# eBox_ACdetect2.net
KiCad netlist of a schematic drawn in Altium Designer
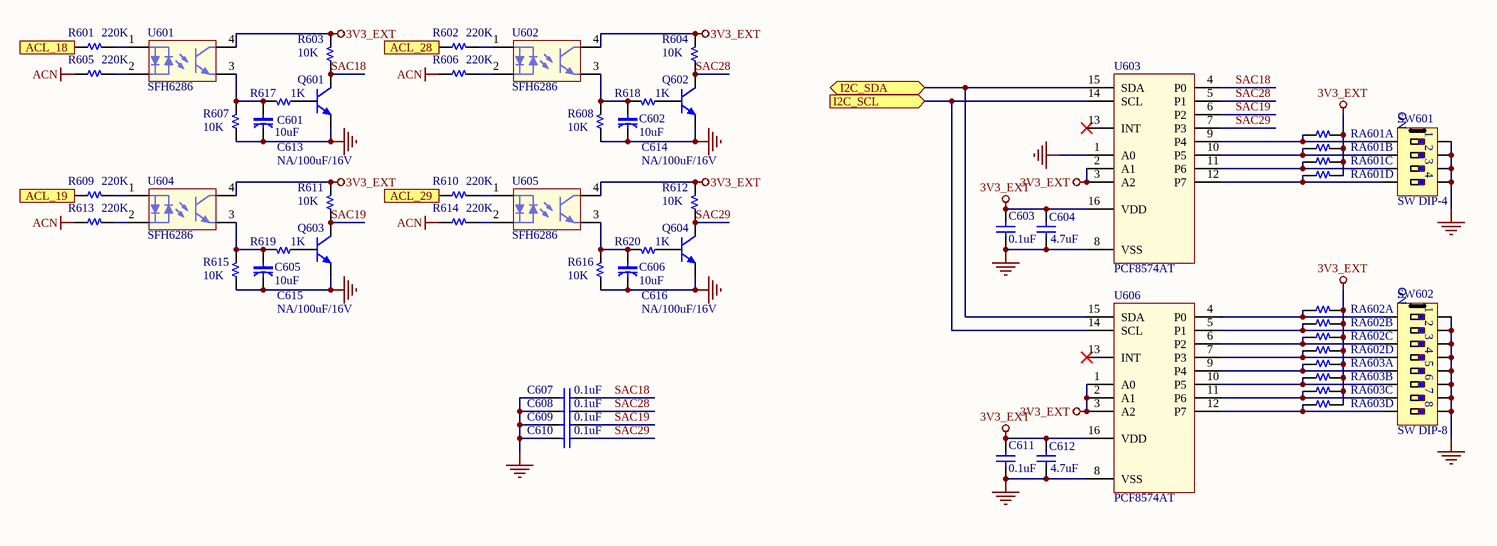
[diagram p0: eBox_ACdetect2.SchDoc]

(export (version "E")
  (design (tool "Eeschema 10.0.6"))
  (components
    (comp (ref "C601")
      (value "10uF")
      (footprint "C 0805")
      (description "CAP CER 0.1UF 50V X7R 0805")
      (libsource (lib "chipfc_altium_libs") (part "Capacitor NP"))
    )
    (comp (ref "C602")
      (value "10uF")
      (footprint "C 0805")
      (description "CAP CER 0.1UF 50V X7R 0805")
      (libsource (lib "chipfc_altium_libs") (part "Capacitor NP"))
    )
    (comp (ref "C603")
      (value "0.1uF")
      (footprint "C 0603")
      (description "CAP CER 0.1UF 50V X7R 0603")
      (libsource (lib "chipfc_altium_libs") (part "Capacitor NP"))
    )
    (comp (ref "C604")
      (value "4.7uF")
      (footprint "C 0603")
      (description "CAP CER 4.7UF 50V X7R 0603")
      (libsource (lib "chipfc_altium_libs") (part "Capacitor NP"))
    )
    (comp (ref "C605")
      (value "10uF")
      (footprint "C 0805")
      (description "CAP CER 0.1UF 50V X7R 0805")
      (libsource (lib "chipfc_altium_libs") (part "Capacitor NP"))
    )
    (comp (ref "C606")
      (value "10uF")
      (footprint "C 0805")
      (description "CAP CER 0.1UF 50V X7R 0805")
      (libsource (lib "chipfc_altium_libs") (part "Capacitor NP"))
    )
    (comp (ref "C607")
      (value "0.1uF")
      (footprint "C 0805")
      (description "CAP CER 0.1UF 50V X7R 0805")
      (libsource (lib "chipfc_altium_libs") (part "Capacitor NP"))
    )
    (comp (ref "C608")
      (value "0.1uF")
      (footprint "C 0805")
      (description "CAP CER 0.1UF 50V X7R 0805")
      (libsource (lib "chipfc_altium_libs") (part "Capacitor NP"))
    )
    (comp (ref "C609")
      (value "0.1uF")
      (footprint "C 0805")
      (description "CAP CER 0.1UF 50V X7R 0805")
      (libsource (lib "chipfc_altium_libs") (part "Capacitor NP"))
    )
    (comp (ref "C610")
      (value "0.1uF")
      (footprint "C 0805")
      (description "CAP CER 0.1UF 50V X7R 0805")
      (libsource (lib "chipfc_altium_libs") (part "Capacitor NP"))
    )
    (comp (ref "C611")
      (value "0.1uF")
      (footprint "C 0603")
      (description "CAP CER 0.1UF 50V X7R 0603")
      (libsource (lib "chipfc_altium_libs") (part "Capacitor NP"))
    )
    (comp (ref "C612")
      (value "4.7uF")
      (footprint "C 0603")
      (description "CAP CER 4.7UF 50V X7R 0603")
      (libsource (lib "chipfc_altium_libs") (part "Capacitor NP"))
    )
    (comp (ref "C613")
      (value "NA/100uF/16V")
      (footprint "CYL/D.200/LS.75-D50H70P20")
      (description "CAP ALUM 100UF 20% 16V RADIAL")
      (libsource (lib "chipfc_altium_libs") (part "Capacitor"))
    )
    (comp (ref "C614")
      (value "NA/100uF/16V")
      (footprint "CYL/D.200/LS.75-D50H70P20")
      (description "CAP ALUM 100UF 20% 16V RADIAL")
      (libsource (lib "chipfc_altium_libs") (part "Capacitor"))
    )
    (comp (ref "C615")
      (value "NA/100uF/16V")
      (footprint "CYL/D.200/LS.75-D50H70P20")
      (description "CAP ALUM 100UF 20% 16V RADIAL")
      (libsource (lib "chipfc_altium_libs") (part "Capacitor"))
    )
    (comp (ref "C616")
      (value "NA/100uF/16V")
      (footprint "CYL/D.200/LS.75-D50H70P20")
      (description "CAP ALUM 100UF 20% 16V RADIAL")
      (libsource (lib "chipfc_altium_libs") (part "Capacitor"))
    )
    (comp (ref "Q601")
      (value "MMBT3904LT1G")
      (footprint "SOT-23")
      (description "TRANS NPN 40V 0.2A SOT23")
      (libsource (lib "chipfc_altium_libs") (part "Transistor NPN"))
    )
    (comp (ref "Q602")
      (value "MMBT3904LT1G")
      (footprint "SOT-23")
      (description "TRANS NPN 40V 0.2A SOT23")
      (libsource (lib "chipfc_altium_libs") (part "Transistor NPN"))
    )
    (comp (ref "Q603")
      (value "MMBT3904LT1G")
      (footprint "SOT-23")
      (description "TRANS NPN 40V 0.2A SOT23")
      (libsource (lib "chipfc_altium_libs") (part "Transistor NPN"))
    )
    (comp (ref "Q604")
      (value "MMBT3904LT1G")
      (footprint "SOT-23")
      (description "TRANS NPN 40V 0.2A SOT23")
      (libsource (lib "chipfc_altium_libs") (part "Transistor NPN"))
    )
    (comp (ref "R601")
      (value "220K")
      (footprint "R 0805")
      (description "RES SMD 220K OHM 1% 1/8W 0805")
      (libsource (lib "chipfc_altium_libs") (part "Resistor"))
    )
    (comp (ref "R602")
      (value "220K")
      (footprint "R 0805")
      (description "RES SMD 220K OHM 1% 1/8W 0805")
      (libsource (lib "chipfc_altium_libs") (part "Resistor"))
    )
    (comp (ref "R603")
      (value "10K")
      (footprint "R 0805")
      (description "RES SMD 10K OHM 1% 1/8W 0805")
      (libsource (lib "chipfc_altium_libs") (part "Resistor"))
    )
    (comp (ref "R604")
      (value "10K")
      (footprint "R 0805")
      (description "RES SMD 10K OHM 1% 1/8W 0805")
      (libsource (lib "chipfc_altium_libs") (part "Resistor"))
    )
    (comp (ref "R605")
      (value "220K")
      (footprint "R 0805")
      (description "RES SMD 220K OHM 1% 1/8W 0805")
      (libsource (lib "chipfc_altium_libs") (part "Resistor"))
    )
    (comp (ref "R606")
      (value "220K")
      (footprint "R 0805")
      (description "RES SMD 220K OHM 1% 1/8W 0805")
      (libsource (lib "chipfc_altium_libs") (part "Resistor"))
    )
    (comp (ref "R607")
      (value "10K")
      (footprint "R 0805")
      (description "RES SMD 10K OHM 1% 1/8W 0805")
      (libsource (lib "chipfc_altium_libs") (part "Resistor"))
    )
    (comp (ref "R608")
      (value "10K")
      (footprint "R 0805")
      (description "RES SMD 10K OHM 1% 1/8W 0805")
      (libsource (lib "chipfc_altium_libs") (part "Resistor"))
    )
    (comp (ref "R609")
      (value "220K")
      (footprint "R 0805")
      (description "RES SMD 220K OHM 1% 1/8W 0805")
      (libsource (lib "chipfc_altium_libs") (part "Resistor"))
    )
    (comp (ref "R610")
      (value "220K")
      (footprint "R 0805")
      (description "RES SMD 220K OHM 1% 1/8W 0805")
      (libsource (lib "chipfc_altium_libs") (part "Resistor"))
    )
    (comp (ref "R611")
      (value "10K")
      (footprint "R 0805")
      (description "RES SMD 10K OHM 1% 1/8W 0805")
      (libsource (lib "chipfc_altium_libs") (part "Resistor"))
    )
    (comp (ref "R612")
      (value "10K")
      (footprint "R 0805")
      (description "RES SMD 10K OHM 1% 1/8W 0805")
      (libsource (lib "chipfc_altium_libs") (part "Resistor"))
    )
    (comp (ref "R613")
      (value "220K")
      (footprint "R 0805")
      (description "RES SMD 220K OHM 1% 1/8W 0805")
      (libsource (lib "chipfc_altium_libs") (part "Resistor"))
    )
    (comp (ref "R614")
      (value "220K")
      (footprint "R 0805")
      (description "RES SMD 220K OHM 1% 1/8W 0805")
      (libsource (lib "chipfc_altium_libs") (part "Resistor"))
    )
    (comp (ref "R615")
      (value "10K")
      (footprint "R 0805")
      (description "RES SMD 10K OHM 1% 1/8W 0805")
      (libsource (lib "chipfc_altium_libs") (part "Resistor"))
    )
    (comp (ref "R616")
      (value "10K")
      (footprint "R 0805")
      (description "RES SMD 10K OHM 1% 1/8W 0805")
      (libsource (lib "chipfc_altium_libs") (part "Resistor"))
    )
    (comp (ref "R617")
      (value "1K")
      (footprint "R 0805")
      (description "RES SMD 1K OHM 5% 1/8W 0805")
      (libsource (lib "chipfc_altium_libs") (part "Resistor"))
    )
    (comp (ref "R618")
      (value "1K")
      (footprint "R 0805")
      (description "RES SMD 1K OHM 5% 1/8W 0805")
      (libsource (lib "chipfc_altium_libs") (part "Resistor"))
    )
    (comp (ref "R619")
      (value "1K")
      (footprint "R 0805")
      (description "RES SMD 1K OHM 5% 1/8W 0805")
      (libsource (lib "chipfc_altium_libs") (part "Resistor"))
    )
    (comp (ref "R620")
      (value "1K")
      (footprint "R 0805")
      (description "RES SMD 1K OHM 5% 1/8W 0805")
      (libsource (lib "chipfc_altium_libs") (part "Resistor"))
    )
    (comp (ref "RA601")
      (value "10K")
      (footprint "RAx4 1206 (3216)")
      (description "10K 1/10W 5% Chip Resistor Array (SMD0603x4)")
      (libsource (lib "chipfc_altium_libs") (part "Resistor Array x4"))
    )
    (comp (ref "RA602")
      (value "10K")
      (footprint "RAx4 1206 (3216)")
      (description "10K 1/10W 5% Chip Resistor Array (SMD0603x4)")
      (libsource (lib "chipfc_altium_libs") (part "Resistor Array x4"))
    )
    (comp (ref "RA603")
      (value "10K")
      (footprint "RAx4 1206 (3216)")
      (description "10K 1/10W 5% Chip Resistor Array (SMD0603x4)")
      (libsource (lib "chipfc_altium_libs") (part "Resistor Array x4"))
    )
    (comp (ref "SW601")
      (value "SW DIP-4")
      (footprint "SW/DIP4")
      (libsource (lib "chipfc_altium_libs") (part "SW DIP-4"))
    )
    (comp (ref "SW602")
      (value "SW DIP-8")
      (footprint "SW/DIP8/300")
      (libsource (lib "chipfc_altium_libs") (part "SW DIP-8"))
    )
    (comp (ref "U601")
      (value "SFH6286")
      (footprint "SOP4 - SFH6286")
      (libsource (lib "chipfc_altium_libs") (part "SFH6286"))
    )
    (comp (ref "U602")
      (value "SFH6286")
      (footprint "SOP4 - SFH6286")
      (libsource (lib "chipfc_altium_libs") (part "SFH6286"))
    )
    (comp (ref "U603")
      (value "PCF8574AT")
      (footprint "SO16/PCF8574AT")
      (description "Remote 8-bit I/O expander for I2C-bus with interrupt")
      (fields (field (name "PART NO") "PCF8574AT/3"))
      (libsource (lib "chipfc_altium_libs") (part "PCF8574AT"))
    )
    (comp (ref "U604")
      (value "SFH6286")
      (footprint "SOP4 - SFH6286")
      (libsource (lib "chipfc_altium_libs") (part "SFH6286"))
    )
    (comp (ref "U605")
      (value "SFH6286")
      (footprint "SOP4 - SFH6286")
      (libsource (lib "chipfc_altium_libs") (part "SFH6286"))
    )
    (comp (ref "U606")
      (value "PCF8574AT")
      (footprint "SO16/PCF8574AT")
      (description "Remote 8-bit I/O expander for I2C-bus with interrupt")
      (fields (field (name "PART NO") "PCF8574AT/3"))
      (libsource (lib "chipfc_altium_libs") (part "PCF8574AT"))
    )
  )
  (nets
    (net (code "1") (name "/ACL_18") (class "Default")
      (node (ref "R601") (pin "1") (pinfunction "1_1") (pintype "passive"))
    )
    (net (code "2") (name "/ACL_19") (class "Default")
      (node (ref "R609") (pin "1") (pinfunction "1_1") (pintype "passive"))
    )
    (net (code "3") (name "/ACL_28") (class "Default")
      (node (ref "R602") (pin "1") (pinfunction "1_1") (pintype "passive"))
    )
    (net (code "4") (name "/ACL_29") (class "Default")
      (node (ref "R610") (pin "1") (pinfunction "1_1") (pintype "passive"))
    )
    (net (code "5") (name "/I2C_SCL") (class "Default")
      (node (ref "U603") (pin "14") (pinfunction "SCL_14") (pintype "passive"))
      (node (ref "U606") (pin "14") (pinfunction "SCL_14") (pintype "passive"))
    )
    (net (code "6") (name "/I2C_SDA") (class "Default")
      (node (ref "U603") (pin "15") (pinfunction "SDA_15") (pintype "passive"))
      (node (ref "U606") (pin "15") (pinfunction "SDA_15") (pintype "passive"))
    )
    (net (code "7") (name "/SAC18") (class "Default")
      (node (ref "C607") (pin "2") (pinfunction "2_2") (pintype "passive"))
      (node (ref "Q601") (pin "3") (pinfunction "C_3") (pintype "passive"))
      (node (ref "R603") (pin "1") (pinfunction "1_1") (pintype "passive"))
      (node (ref "U603") (pin "4") (pinfunction "P0_4") (pintype "passive"))
    )
    (net (code "8") (name "/SAC19") (class "Default")
      (node (ref "C609") (pin "2") (pinfunction "2_2") (pintype "passive"))
      (node (ref "Q603") (pin "3") (pinfunction "C_3") (pintype "passive"))
      (node (ref "R611") (pin "1") (pinfunction "1_1") (pintype "passive"))
      (node (ref "U603") (pin "6") (pinfunction "P2_6") (pintype "passive"))
    )
    (net (code "9") (name "/SAC28") (class "Default")
      (node (ref "C608") (pin "2") (pinfunction "2_2") (pintype "passive"))
      (node (ref "Q602") (pin "3") (pinfunction "C_3") (pintype "passive"))
      (node (ref "R604") (pin "1") (pinfunction "1_1") (pintype "passive"))
      (node (ref "U603") (pin "5") (pinfunction "P1_5") (pintype "passive"))
    )
    (net (code "10") (name "/SAC29") (class "Default")
      (node (ref "C610") (pin "2") (pinfunction "2_2") (pintype "passive"))
      (node (ref "Q604") (pin "3") (pinfunction "C_3") (pintype "passive"))
      (node (ref "R612") (pin "1") (pinfunction "1_1") (pintype "passive"))
      (node (ref "U603") (pin "7") (pinfunction "P3_7") (pintype "passive"))
    )
    (net (code "11") (name "3V3_EXT") (class "Default")
      (node (ref "C603") (pin "1") (pinfunction "1_1") (pintype "passive"))
      (node (ref "C604") (pin "1") (pinfunction "1_1") (pintype "passive"))
      (node (ref "C611") (pin "1") (pinfunction "1_1") (pintype "passive"))
      (node (ref "C612") (pin "1") (pinfunction "1_1") (pintype "passive"))
      (node (ref "R603") (pin "2") (pinfunction "2_2") (pintype "passive"))
      (node (ref "R604") (pin "2") (pinfunction "2_2") (pintype "passive"))
      (node (ref "R611") (pin "2") (pinfunction "2_2") (pintype "passive"))
      (node (ref "R612") (pin "2") (pinfunction "2_2") (pintype "passive"))
      (node (ref "RA601") (pin "5") (pinfunction "5_5") (pintype "passive"))
      (node (ref "RA601") (pin "6") (pinfunction "6_6") (pintype "passive"))
      (node (ref "RA601") (pin "7") (pinfunction "7_7") (pintype "passive"))
      (node (ref "RA601") (pin "8") (pinfunction "8_8") (pintype "passive"))
      (node (ref "RA602") (pin "5") (pinfunction "5_5") (pintype "passive"))
      (node (ref "RA602") (pin "6") (pinfunction "6_6") (pintype "passive"))
      (node (ref "RA602") (pin "7") (pinfunction "7_7") (pintype "passive"))
      (node (ref "RA602") (pin "8") (pinfunction "8_8") (pintype "passive"))
      (node (ref "RA603") (pin "5") (pinfunction "5_5") (pintype "passive"))
      (node (ref "RA603") (pin "6") (pinfunction "6_6") (pintype "passive"))
      (node (ref "RA603") (pin "7") (pinfunction "7_7") (pintype "passive"))
      (node (ref "RA603") (pin "8") (pinfunction "8_8") (pintype "passive"))
      (node (ref "U601") (pin "4") (pinfunction "C_4") (pintype "passive"))
      (node (ref "U602") (pin "4") (pinfunction "C_4") (pintype "passive"))
      (node (ref "U603") (pin "16") (pinfunction "VDD_16") (pintype "passive"))
      (node (ref "U603") (pin "2") (pinfunction "A1_2") (pintype "passive"))
      (node (ref "U603") (pin "3") (pinfunction "A2_3") (pintype "passive"))
      (node (ref "U604") (pin "4") (pinfunction "C_4") (pintype "passive"))
      (node (ref "U605") (pin "4") (pinfunction "C_4") (pintype "passive"))
      (node (ref "U606") (pin "1") (pinfunction "A0_1") (pintype "passive"))
      (node (ref "U606") (pin "16") (pinfunction "VDD_16") (pintype "passive"))
      (node (ref "U606") (pin "2") (pinfunction "A1_2") (pintype "passive"))
      (node (ref "U606") (pin "3") (pinfunction "A2_3") (pintype "passive"))
    )
    (net (code "12") (name "ACN") (class "Default")
      (node (ref "R605") (pin "1") (pinfunction "1_1") (pintype "passive"))
      (node (ref "R606") (pin "1") (pinfunction "1_1") (pintype "passive"))
      (node (ref "R613") (pin "1") (pinfunction "1_1") (pintype "passive"))
      (node (ref "R614") (pin "1") (pinfunction "1_1") (pintype "passive"))
    )
    (net (code "13") (name "GND") (class "Default")
      (node (ref "C601") (pin "2") (pinfunction "2_2") (pintype "passive"))
      (node (ref "C602") (pin "2") (pinfunction "2_2") (pintype "passive"))
      (node (ref "C603") (pin "2") (pinfunction "2_2") (pintype "passive"))
      (node (ref "C604") (pin "2") (pinfunction "2_2") (pintype "passive"))
      (node (ref "C605") (pin "2") (pinfunction "2_2") (pintype "passive"))
      (node (ref "C606") (pin "2") (pinfunction "2_2") (pintype "passive"))
      (node (ref "C607") (pin "1") (pinfunction "1_1") (pintype "passive"))
      (node (ref "C608") (pin "1") (pinfunction "1_1") (pintype "passive"))
      (node (ref "C609") (pin "1") (pinfunction "1_1") (pintype "passive"))
      (node (ref "C610") (pin "1") (pinfunction "1_1") (pintype "passive"))
      (node (ref "C611") (pin "2") (pinfunction "2_2") (pintype "passive"))
      (node (ref "C612") (pin "2") (pinfunction "2_2") (pintype "passive"))
      (node (ref "C613") (pin "2") (pinfunction "2_2") (pintype "passive"))
      (node (ref "C614") (pin "2") (pinfunction "2_2") (pintype "passive"))
      (node (ref "C615") (pin "2") (pinfunction "2_2") (pintype "passive"))
      (node (ref "C616") (pin "2") (pinfunction "2_2") (pintype "passive"))
      (node (ref "Q601") (pin "2") (pinfunction "E_2") (pintype "passive"))
      (node (ref "Q602") (pin "2") (pinfunction "E_2") (pintype "passive"))
      (node (ref "Q603") (pin "2") (pinfunction "E_2") (pintype "passive"))
      (node (ref "Q604") (pin "2") (pinfunction "E_2") (pintype "passive"))
      (node (ref "R607") (pin "1") (pinfunction "1_1") (pintype "passive"))
      (node (ref "R608") (pin "1") (pinfunction "1_1") (pintype "passive"))
      (node (ref "R615") (pin "1") (pinfunction "1_1") (pintype "passive"))
      (node (ref "R616") (pin "1") (pinfunction "1_1") (pintype "passive"))
      (node (ref "SW601") (pin "1") (pinfunction "1_1") (pintype "passive"))
      (node (ref "SW601") (pin "2") (pinfunction "2_2") (pintype "passive"))
      (node (ref "SW601") (pin "3") (pinfunction "3_3") (pintype "passive"))
      (node (ref "SW601") (pin "4") (pinfunction "4_4") (pintype "passive"))
      (node (ref "SW602") (pin "1") (pinfunction "1_1") (pintype "passive"))
      (node (ref "SW602") (pin "2") (pinfunction "2_2") (pintype "passive"))
      (node (ref "SW602") (pin "3") (pinfunction "3_3") (pintype "passive"))
      (node (ref "SW602") (pin "4") (pinfunction "4_4") (pintype "passive"))
      (node (ref "SW602") (pin "5") (pinfunction "5_5") (pintype "passive"))
      (node (ref "SW602") (pin "6") (pinfunction "6_6") (pintype "passive"))
      (node (ref "SW602") (pin "7") (pinfunction "7_7") (pintype "passive"))
      (node (ref "SW602") (pin "8") (pinfunction "8_8") (pintype "passive"))
      (node (ref "U603") (pin "1") (pinfunction "A0_1") (pintype "passive"))
      (node (ref "U603") (pin "8") (pinfunction "VSS_8") (pintype "passive"))
      (node (ref "U606") (pin "8") (pinfunction "VSS_8") (pintype "passive"))
    )
    (net (code "14") (name "Net-(Q601-B)") (class "Default")
      (node (ref "Q601") (pin "1") (pinfunction "B_1") (pintype "passive"))
      (node (ref "R617") (pin "1") (pinfunction "1_1") (pintype "passive"))
    )
    (net (code "15") (name "Net-(Q602-B)") (class "Default")
      (node (ref "Q602") (pin "1") (pinfunction "B_1") (pintype "passive"))
      (node (ref "R618") (pin "1") (pinfunction "1_1") (pintype "passive"))
    )
    (net (code "16") (name "Net-(Q603-B)") (class "Default")
      (node (ref "Q603") (pin "1") (pinfunction "B_1") (pintype "passive"))
      (node (ref "R619") (pin "1") (pinfunction "1_1") (pintype "passive"))
    )
    (net (code "17") (name "Net-(Q604-B)") (class "Default")
      (node (ref "Q604") (pin "1") (pinfunction "B_1") (pintype "passive"))
      (node (ref "R620") (pin "1") (pinfunction "1_1") (pintype "passive"))
    )
    (net (code "18") (name "Net-(U601-A{slash}C)") (class "Default")
      (node (ref "R601") (pin "2") (pinfunction "2_2") (pintype "passive"))
      (node (ref "U601") (pin "1") (pinfunction "A/C_1") (pintype "passive"))
    )
    (net (code "19") (name "Net-(U601-C{slash}A)") (class "Default")
      (node (ref "R605") (pin "2") (pinfunction "2_2") (pintype "passive"))
      (node (ref "U601") (pin "2") (pinfunction "C/A_2") (pintype "passive"))
    )
    (net (code "20") (name "Net-(U601-E)") (class "Default")
      (node (ref "C601") (pin "1") (pinfunction "1_1") (pintype "passive"))
      (node (ref "C613") (pin "1") (pinfunction "1_1") (pintype "passive"))
      (node (ref "R607") (pin "2") (pinfunction "2_2") (pintype "passive"))
      (node (ref "R617") (pin "2") (pinfunction "2_2") (pintype "passive"))
      (node (ref "U601") (pin "3") (pinfunction "E_3") (pintype "passive"))
    )
    (net (code "21") (name "Net-(U602-A{slash}C)") (class "Default")
      (node (ref "R602") (pin "2") (pinfunction "2_2") (pintype "passive"))
      (node (ref "U602") (pin "1") (pinfunction "A/C_1") (pintype "passive"))
    )
    (net (code "22") (name "Net-(U602-C{slash}A)") (class "Default")
      (node (ref "R606") (pin "2") (pinfunction "2_2") (pintype "passive"))
      (node (ref "U602") (pin "2") (pinfunction "C/A_2") (pintype "passive"))
    )
    (net (code "23") (name "Net-(U602-E)") (class "Default")
      (node (ref "C602") (pin "1") (pinfunction "1_1") (pintype "passive"))
      (node (ref "C614") (pin "1") (pinfunction "1_1") (pintype "passive"))
      (node (ref "R608") (pin "2") (pinfunction "2_2") (pintype "passive"))
      (node (ref "R618") (pin "2") (pinfunction "2_2") (pintype "passive"))
      (node (ref "U602") (pin "3") (pinfunction "E_3") (pintype "passive"))
    )
    (net (code "24") (name "Net-(U603-P4)") (class "Default")
      (node (ref "RA601") (pin "1") (pinfunction "1_1") (pintype "passive"))
      (node (ref "SW601") (pin "8") (pinfunction "8_8") (pintype "passive"))
      (node (ref "U603") (pin "9") (pinfunction "P4_9") (pintype "passive"))
    )
    (net (code "25") (name "Net-(U603-P5)") (class "Default")
      (node (ref "RA601") (pin "2") (pinfunction "2_2") (pintype "passive"))
      (node (ref "SW601") (pin "7") (pinfunction "7_7") (pintype "passive"))
      (node (ref "U603") (pin "10") (pinfunction "P5_10") (pintype "passive"))
    )
    (net (code "26") (name "Net-(U603-P6)") (class "Default")
      (node (ref "RA601") (pin "3") (pinfunction "3_3") (pintype "passive"))
      (node (ref "SW601") (pin "6") (pinfunction "6_6") (pintype "passive"))
      (node (ref "U603") (pin "11") (pinfunction "P6_11") (pintype "passive"))
    )
    (net (code "27") (name "Net-(U603-P7)") (class "Default")
      (node (ref "RA601") (pin "4") (pinfunction "4_4") (pintype "passive"))
      (node (ref "SW601") (pin "5") (pinfunction "5_5") (pintype "passive"))
      (node (ref "U603") (pin "12") (pinfunction "P7_12") (pintype "passive"))
    )
    (net (code "28") (name "Net-(U604-A{slash}C)") (class "Default")
      (node (ref "R609") (pin "2") (pinfunction "2_2") (pintype "passive"))
      (node (ref "U604") (pin "1") (pinfunction "A/C_1") (pintype "passive"))
    )
    (net (code "29") (name "Net-(U604-C{slash}A)") (class "Default")
      (node (ref "R613") (pin "2") (pinfunction "2_2") (pintype "passive"))
      (node (ref "U604") (pin "2") (pinfunction "C/A_2") (pintype "passive"))
    )
    (net (code "30") (name "Net-(U604-E)") (class "Default")
      (node (ref "C605") (pin "1") (pinfunction "1_1") (pintype "passive"))
      (node (ref "C615") (pin "1") (pinfunction "1_1") (pintype "passive"))
      (node (ref "R615") (pin "2") (pinfunction "2_2") (pintype "passive"))
      (node (ref "R619") (pin "2") (pinfunction "2_2") (pintype "passive"))
      (node (ref "U604") (pin "3") (pinfunction "E_3") (pintype "passive"))
    )
    (net (code "31") (name "Net-(U605-A{slash}C)") (class "Default")
      (node (ref "R610") (pin "2") (pinfunction "2_2") (pintype "passive"))
      (node (ref "U605") (pin "1") (pinfunction "A/C_1") (pintype "passive"))
    )
    (net (code "32") (name "Net-(U605-C{slash}A)") (class "Default")
      (node (ref "R614") (pin "2") (pinfunction "2_2") (pintype "passive"))
      (node (ref "U605") (pin "2") (pinfunction "C/A_2") (pintype "passive"))
    )
    (net (code "33") (name "Net-(U605-E)") (class "Default")
      (node (ref "C606") (pin "1") (pinfunction "1_1") (pintype "passive"))
      (node (ref "C616") (pin "1") (pinfunction "1_1") (pintype "passive"))
      (node (ref "R616") (pin "2") (pinfunction "2_2") (pintype "passive"))
      (node (ref "R620") (pin "2") (pinfunction "2_2") (pintype "passive"))
      (node (ref "U605") (pin "3") (pinfunction "E_3") (pintype "passive"))
    )
    (net (code "34") (name "Net-(U606-P0)") (class "Default")
      (node (ref "RA602") (pin "1") (pinfunction "1_1") (pintype "passive"))
      (node (ref "SW602") (pin "16") (pinfunction "16_16") (pintype "passive"))
      (node (ref "U606") (pin "4") (pinfunction "P0_4") (pintype "passive"))
    )
    (net (code "35") (name "Net-(U606-P1)") (class "Default")
      (node (ref "RA602") (pin "2") (pinfunction "2_2") (pintype "passive"))
      (node (ref "SW602") (pin "15") (pinfunction "15_15") (pintype "passive"))
      (node (ref "U606") (pin "5") (pinfunction "P1_5") (pintype "passive"))
    )
    (net (code "36") (name "Net-(U606-P2)") (class "Default")
      (node (ref "RA602") (pin "3") (pinfunction "3_3") (pintype "passive"))
      (node (ref "SW602") (pin "14") (pinfunction "14_14") (pintype "passive"))
      (node (ref "U606") (pin "6") (pinfunction "P2_6") (pintype "passive"))
    )
    (net (code "37") (name "Net-(U606-P3)") (class "Default")
      (node (ref "RA602") (pin "4") (pinfunction "4_4") (pintype "passive"))
      (node (ref "SW602") (pin "13") (pinfunction "13_13") (pintype "passive"))
      (node (ref "U606") (pin "7") (pinfunction "P3_7") (pintype "passive"))
    )
    (net (code "38") (name "Net-(U606-P4)") (class "Default")
      (node (ref "RA603") (pin "1") (pinfunction "1_1") (pintype "passive"))
      (node (ref "SW602") (pin "12") (pinfunction "12_12") (pintype "passive"))
      (node (ref "U606") (pin "9") (pinfunction "P4_9") (pintype "passive"))
    )
    (net (code "39") (name "Net-(U606-P5)") (class "Default")
      (node (ref "RA603") (pin "2") (pinfunction "2_2") (pintype "passive"))
      (node (ref "SW602") (pin "11") (pinfunction "11_11") (pintype "passive"))
      (node (ref "U606") (pin "10") (pinfunction "P5_10") (pintype "passive"))
    )
    (net (code "40") (name "Net-(U606-P6)") (class "Default")
      (node (ref "RA603") (pin "3") (pinfunction "3_3") (pintype "passive"))
      (node (ref "SW602") (pin "10") (pinfunction "10_10") (pintype "passive"))
      (node (ref "U606") (pin "11") (pinfunction "P6_11") (pintype "passive"))
    )
    (net (code "41") (name "Net-(U606-P7)") (class "Default")
      (node (ref "RA603") (pin "4") (pinfunction "4_4") (pintype "passive"))
      (node (ref "SW602") (pin "9") (pinfunction "9_9") (pintype "passive"))
      (node (ref "U606") (pin "12") (pinfunction "P7_12") (pintype "passive"))
    )
    (net (code "42") (name "unconnected-(U603-INT-Pad13)") (class "Default")
      (node (ref "U603") (pin "13") (pinfunction "INT_13") (pintype "passive+no_connect"))
    )
    (net (code "43") (name "unconnected-(U606-INT-Pad13)") (class "Default")
      (node (ref "U606") (pin "13") (pinfunction "INT_13") (pintype "passive+no_connect"))
    )
  )
)
